# 3_RK3588_POWER.net
KiCad netlist of a schematic drawn in Altium Designer
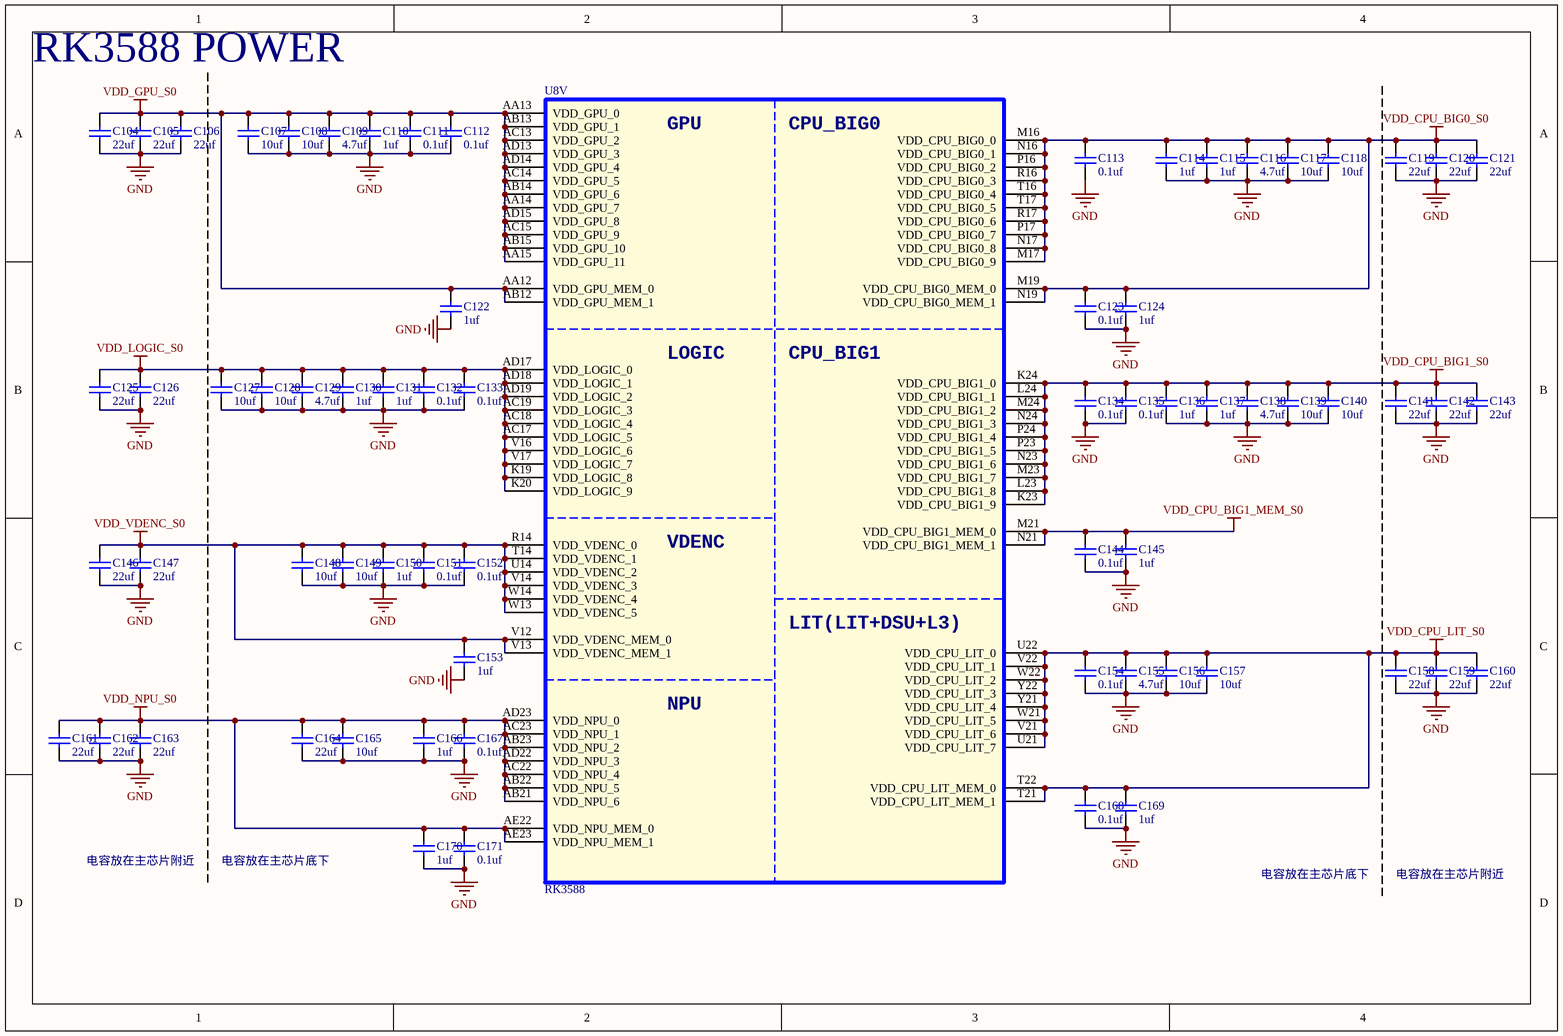
[diagram p0: 3.RK3588_POWER.SchDoc]

(export (version "E")
  (design (tool "Eeschema 10.0.6"))
  (components
    (comp (ref "C104")
      (value "22uf")
      (footprint "0.PCB1:C0603_L")
      (description "贴片电容/MLCC电容")
      (libsource (lib "RK3588") (part "C"))
    )
    (comp (ref "C105")
      (value "22uf")
      (footprint "0.PCB1:C0603_L")
      (description "贴片电容/MLCC电容")
      (libsource (lib "RK3588") (part "C"))
    )
    (comp (ref "C106")
      (value "22uf")
      (footprint "0.PCB1:C0603_L")
      (description "贴片电容/MLCC电容")
      (libsource (lib "RK3588") (part "C"))
    )
    (comp (ref "C107")
      (value "10uf")
      (footprint "0.PCB1:C0402_L")
      (description "贴片电容/MLCC电容")
      (libsource (lib "RK3588") (part "C"))
    )
    (comp (ref "C108")
      (value "10uf")
      (footprint "0.PCB1:C0402_L")
      (description "贴片电容/MLCC电容")
      (libsource (lib "RK3588") (part "C"))
    )
    (comp (ref "C109")
      (value "4.7uf")
      (footprint "0.PCB1:C0402_L")
      (description "贴片电容/MLCC电容")
      (libsource (lib "RK3588") (part "C"))
    )
    (comp (ref "C110")
      (value "1uf")
      (footprint "0.PCB1:C0201_L")
      (description "贴片电容/MLCC电容")
      (libsource (lib "RK3588") (part "C"))
    )
    (comp (ref "C111")
      (value "0.1uf")
      (footprint "0.PCB1:C0201_L")
      (description "贴片电容/MLCC电容")
      (libsource (lib "RK3588") (part "C"))
    )
    (comp (ref "C112")
      (value "0.1uf")
      (footprint "0.PCB1:C0201_L")
      (description "贴片电容/MLCC电容")
      (libsource (lib "RK3588") (part "C"))
    )
    (comp (ref "C113")
      (value "0.1uf")
      (footprint "0.PCB1:C0201_L")
      (description "贴片电容/MLCC电容")
      (libsource (lib "RK3588") (part "C"))
    )
    (comp (ref "C114")
      (value "1uf")
      (footprint "0.PCB1:C0201_L")
      (description "贴片电容/MLCC电容")
      (libsource (lib "RK3588") (part "C"))
    )
    (comp (ref "C115")
      (value "1uf")
      (footprint "0.PCB1:C0201_L")
      (description "贴片电容/MLCC电容")
      (libsource (lib "RK3588") (part "C"))
    )
    (comp (ref "C116")
      (value "4.7uf")
      (footprint "0.PCB1:C0201_L")
      (description "贴片电容/MLCC电容")
      (libsource (lib "RK3588") (part "C"))
    )
    (comp (ref "C117")
      (value "10uf")
      (footprint "0.PCB1:C0402_L")
      (description "贴片电容/MLCC电容")
      (libsource (lib "RK3588") (part "C"))
    )
    (comp (ref "C118")
      (value "10uf")
      (footprint "0.PCB1:C0402_L")
      (description "贴片电容/MLCC电容")
      (libsource (lib "RK3588") (part "C"))
    )
    (comp (ref "C119")
      (value "22uf")
      (footprint "0.PCB1:C0603_L")
      (description "贴片电容/MLCC电容")
      (libsource (lib "RK3588") (part "C"))
    )
    (comp (ref "C120")
      (value "22uf")
      (footprint "0.PCB1:C0603_L")
      (description "贴片电容/MLCC电容")
      (libsource (lib "RK3588") (part "C"))
    )
    (comp (ref "C121")
      (value "22uf")
      (footprint "0.PCB1:C0603_L")
      (description "贴片电容/MLCC电容")
      (libsource (lib "RK3588") (part "C"))
    )
    (comp (ref "C122")
      (value "1uf")
      (footprint "0.PCB1:C0201_L")
      (description "贴片电容/MLCC电容")
      (libsource (lib "RK3588") (part "C"))
    )
    (comp (ref "C123")
      (value "0.1uf")
      (footprint "0.PCB1:C0201_L")
      (description "贴片电容/MLCC电容")
      (libsource (lib "RK3588") (part "C"))
    )
    (comp (ref "C124")
      (value "1uf")
      (footprint "0.PCB1:C0201_L")
      (description "贴片电容/MLCC电容")
      (libsource (lib "RK3588") (part "C"))
    )
    (comp (ref "C125")
      (value "22uf")
      (footprint "0.PCB1:C0603_L")
      (description "贴片电容/MLCC电容")
      (libsource (lib "RK3588") (part "C"))
    )
    (comp (ref "C126")
      (value "22uf")
      (footprint "0.PCB1:C0603_L")
      (description "贴片电容/MLCC电容")
      (libsource (lib "RK3588") (part "C"))
    )
    (comp (ref "C127")
      (value "10uf")
      (footprint "0.PCB1:C0402_L")
      (description "贴片电容/MLCC电容")
      (libsource (lib "RK3588") (part "C"))
    )
    (comp (ref "C128")
      (value "10uf")
      (footprint "0.PCB1:C0402_L")
      (description "贴片电容/MLCC电容")
      (libsource (lib "RK3588") (part "C"))
    )
    (comp (ref "C129")
      (value "4.7uf")
      (footprint "0.PCB1:C0402_L")
      (description "贴片电容/MLCC电容")
      (libsource (lib "RK3588") (part "C"))
    )
    (comp (ref "C130")
      (value "1uf")
      (footprint "0.PCB1:C0201_L")
      (description "贴片电容/MLCC电容")
      (libsource (lib "RK3588") (part "C"))
    )
    (comp (ref "C131")
      (value "1uf")
      (footprint "0.PCB1:C0201_L")
      (description "贴片电容/MLCC电容")
      (libsource (lib "RK3588") (part "C"))
    )
    (comp (ref "C132")
      (value "0.1uf")
      (footprint "0.PCB1:C0201_L")
      (description "贴片电容/MLCC电容")
      (libsource (lib "RK3588") (part "C"))
    )
    (comp (ref "C133")
      (value "0.1uf")
      (footprint "0.PCB1:C0201_L")
      (description "贴片电容/MLCC电容")
      (libsource (lib "RK3588") (part "C"))
    )
    (comp (ref "C134")
      (value "0.1uf")
      (footprint "0.PCB1:C0201_L")
      (description "贴片电容/MLCC电容")
      (libsource (lib "RK3588") (part "C"))
    )
    (comp (ref "C135")
      (value "0.1uf")
      (footprint "0.PCB1:C0201_L")
      (description "贴片电容/MLCC电容")
      (libsource (lib "RK3588") (part "C"))
    )
    (comp (ref "C136")
      (value "1uf")
      (footprint "0.PCB1:C0201_L")
      (description "贴片电容/MLCC电容")
      (libsource (lib "RK3588") (part "C"))
    )
    (comp (ref "C137")
      (value "1uf")
      (footprint "0.PCB1:C0201_L")
      (description "贴片电容/MLCC电容")
      (libsource (lib "RK3588") (part "C"))
    )
    (comp (ref "C138")
      (value "4.7uf")
      (footprint "0.PCB1:C0402_L")
      (description "贴片电容/MLCC电容")
      (libsource (lib "RK3588") (part "C"))
    )
    (comp (ref "C139")
      (value "10uf")
      (footprint "0.PCB1:C0402_L")
      (description "贴片电容/MLCC电容")
      (libsource (lib "RK3588") (part "C"))
    )
    (comp (ref "C140")
      (value "10uf")
      (footprint "0.PCB1:C0402_L")
      (description "贴片电容/MLCC电容")
      (libsource (lib "RK3588") (part "C"))
    )
    (comp (ref "C141")
      (value "22uf")
      (footprint "0.PCB1:C0603_L")
      (description "贴片电容/MLCC电容")
      (libsource (lib "RK3588") (part "C"))
    )
    (comp (ref "C142")
      (value "22uf")
      (footprint "0.PCB1:C0603_L")
      (description "贴片电容/MLCC电容")
      (libsource (lib "RK3588") (part "C"))
    )
    (comp (ref "C143")
      (value "22uf")
      (footprint "0.PCB1:C0603_L")
      (description "贴片电容/MLCC电容")
      (libsource (lib "RK3588") (part "C"))
    )
    (comp (ref "C144")
      (value "0.1uf")
      (footprint "0.PCB1:C0201_L")
      (description "贴片电容/MLCC电容")
      (libsource (lib "RK3588") (part "C"))
    )
    (comp (ref "C145")
      (value "1uf")
      (footprint "0.PCB1:C0201_L")
      (description "贴片电容/MLCC电容")
      (libsource (lib "RK3588") (part "C"))
    )
    (comp (ref "C146")
      (value "22uf")
      (footprint "0.PCB1:C0603_L")
      (description "贴片电容/MLCC电容")
      (libsource (lib "RK3588") (part "C"))
    )
    (comp (ref "C147")
      (value "22uf")
      (footprint "0.PCB1:C0603_L")
      (description "贴片电容/MLCC电容")
      (libsource (lib "RK3588") (part "C"))
    )
    (comp (ref "C148")
      (value "10uf")
      (footprint "0.PCB1:C0402_L")
      (description "贴片电容/MLCC电容")
      (libsource (lib "RK3588") (part "C"))
    )
    (comp (ref "C149")
      (value "10uf")
      (footprint "0.PCB1:C0402_L")
      (description "贴片电容/MLCC电容")
      (libsource (lib "RK3588") (part "C"))
    )
    (comp (ref "C150")
      (value "1uf")
      (footprint "0.PCB1:C0201_L")
      (description "贴片电容/MLCC电容")
      (libsource (lib "RK3588") (part "C"))
    )
    (comp (ref "C151")
      (value "0.1uf")
      (footprint "0.PCB1:C0201_L")
      (description "贴片电容/MLCC电容")
      (libsource (lib "RK3588") (part "C"))
    )
    (comp (ref "C152")
      (value "0.1uf")
      (footprint "0.PCB1:C0201_L")
      (description "贴片电容/MLCC电容")
      (libsource (lib "RK3588") (part "C"))
    )
    (comp (ref "C153")
      (value "1uf")
      (footprint "0.PCB1:C0201_L")
      (description "贴片电容/MLCC电容")
      (libsource (lib "RK3588") (part "C"))
    )
    (comp (ref "C154")
      (value "0.1uf")
      (footprint "0.PCB1:C0201_L")
      (description "贴片电容/MLCC电容")
      (libsource (lib "RK3588") (part "C"))
    )
    (comp (ref "C155")
      (value "4.7uf")
      (footprint "0.PCB1:C0402_L")
      (description "贴片电容/MLCC电容")
      (libsource (lib "RK3588") (part "C"))
    )
    (comp (ref "C156")
      (value "10uf")
      (footprint "0.PCB1:C0402_L")
      (description "贴片电容/MLCC电容")
      (libsource (lib "RK3588") (part "C"))
    )
    (comp (ref "C157")
      (value "10uf")
      (footprint "0.PCB1:C0402_L")
      (description "贴片电容/MLCC电容")
      (libsource (lib "RK3588") (part "C"))
    )
    (comp (ref "C158")
      (value "22uf")
      (footprint "0.PCB1:C0603_L")
      (description "贴片电容/MLCC电容")
      (libsource (lib "RK3588") (part "C"))
    )
    (comp (ref "C159")
      (value "22uf")
      (footprint "0.PCB1:C0603_L")
      (description "贴片电容/MLCC电容")
      (libsource (lib "RK3588") (part "C"))
    )
    (comp (ref "C160")
      (value "22uf")
      (footprint "0.PCB1:C0603_L")
      (description "贴片电容/MLCC电容")
      (libsource (lib "RK3588") (part "C"))
    )
    (comp (ref "C161")
      (value "22uf")
      (footprint "0.PCB1:C0603_L")
      (description "贴片电容/MLCC电容")
      (libsource (lib "RK3588") (part "C"))
    )
    (comp (ref "C162")
      (value "22uf")
      (footprint "0.PCB1:C0603_L")
      (description "贴片电容/MLCC电容")
      (libsource (lib "RK3588") (part "C"))
    )
    (comp (ref "C163")
      (value "22uf")
      (footprint "0.PCB1:C0603_L")
      (description "贴片电容/MLCC电容")
      (libsource (lib "RK3588") (part "C"))
    )
    (comp (ref "C164")
      (value "22uf")
      (footprint "0.PCB1:C0402_L")
      (description "贴片电容/MLCC电容")
      (libsource (lib "RK3588") (part "C"))
    )
    (comp (ref "C165")
      (value "10uf")
      (footprint "0.PCB1:C0402_L")
      (description "贴片电容/MLCC电容")
      (libsource (lib "RK3588") (part "C"))
    )
    (comp (ref "C166")
      (value "1uf")
      (footprint "0.PCB1:C0201_L")
      (description "贴片电容/MLCC电容")
      (libsource (lib "RK3588") (part "C"))
    )
    (comp (ref "C167")
      (value "0.1uf")
      (footprint "0.PCB1:C0201_L")
      (description "贴片电容/MLCC电容")
      (libsource (lib "RK3588") (part "C"))
    )
    (comp (ref "C168")
      (value "0.1uf")
      (footprint "0.PCB1:C0201_L")
      (description "贴片电容/MLCC电容")
      (libsource (lib "RK3588") (part "C"))
    )
    (comp (ref "C169")
      (value "1uf")
      (footprint "0.PCB1:C0201_L")
      (description "贴片电容/MLCC电容")
      (libsource (lib "RK3588") (part "C"))
    )
    (comp (ref "C170")
      (value "1uf")
      (footprint "0.PCB1:C0201_L")
      (description "贴片电容/MLCC电容")
      (libsource (lib "RK3588") (part "C"))
    )
    (comp (ref "C171")
      (value "0.1uf")
      (footprint "0.PCB1:C0201_L")
      (description "贴片电容/MLCC电容")
      (libsource (lib "RK3588") (part "C"))
    )
    (comp (ref "U8")
      (value "RK3588")
      (footprint "0.PCB1:BGA1088_23R00X23R00X2R00")
      (description "ROCKCHIP SOC")
      (libsource (lib "RK3588") (part "SOC_RK3588"))
    )
  )
  (nets
    (net (code "1") (name "GND") (class "Default")
      (node (ref "C104") (pin "1") (pinfunction "1_1") (pintype "passive"))
      (node (ref "C105") (pin "1") (pinfunction "1_1") (pintype "passive"))
      (node (ref "C106") (pin "1") (pinfunction "1_1") (pintype "passive"))
      (node (ref "C107") (pin "1") (pinfunction "1_1") (pintype "passive"))
      (node (ref "C108") (pin "1") (pinfunction "1_1") (pintype "passive"))
      (node (ref "C109") (pin "1") (pinfunction "1_1") (pintype "passive"))
      (node (ref "C110") (pin "1") (pinfunction "1_1") (pintype "passive"))
      (node (ref "C111") (pin "1") (pinfunction "1_1") (pintype "passive"))
      (node (ref "C112") (pin "1") (pinfunction "1_1") (pintype "passive"))
      (node (ref "C113") (pin "1") (pinfunction "1_1") (pintype "passive"))
      (node (ref "C114") (pin "1") (pinfunction "1_1") (pintype "passive"))
      (node (ref "C115") (pin "1") (pinfunction "1_1") (pintype "passive"))
      (node (ref "C116") (pin "1") (pinfunction "1_1") (pintype "passive"))
      (node (ref "C117") (pin "1") (pinfunction "1_1") (pintype "passive"))
      (node (ref "C118") (pin "1") (pinfunction "1_1") (pintype "passive"))
      (node (ref "C119") (pin "1") (pinfunction "1_1") (pintype "passive"))
      (node (ref "C120") (pin "1") (pinfunction "1_1") (pintype "passive"))
      (node (ref "C121") (pin "1") (pinfunction "1_1") (pintype "passive"))
      (node (ref "C122") (pin "1") (pinfunction "1_1") (pintype "passive"))
      (node (ref "C123") (pin "1") (pinfunction "1_1") (pintype "passive"))
      (node (ref "C124") (pin "1") (pinfunction "1_1") (pintype "passive"))
      (node (ref "C125") (pin "1") (pinfunction "1_1") (pintype "passive"))
      (node (ref "C126") (pin "1") (pinfunction "1_1") (pintype "passive"))
      (node (ref "C127") (pin "1") (pinfunction "1_1") (pintype "passive"))
      (node (ref "C128") (pin "1") (pinfunction "1_1") (pintype "passive"))
      (node (ref "C129") (pin "1") (pinfunction "1_1") (pintype "passive"))
      (node (ref "C130") (pin "1") (pinfunction "1_1") (pintype "passive"))
      (node (ref "C131") (pin "1") (pinfunction "1_1") (pintype "passive"))
      (node (ref "C132") (pin "1") (pinfunction "1_1") (pintype "passive"))
      (node (ref "C133") (pin "1") (pinfunction "1_1") (pintype "passive"))
      (node (ref "C134") (pin "1") (pinfunction "1_1") (pintype "passive"))
      (node (ref "C135") (pin "1") (pinfunction "1_1") (pintype "passive"))
      (node (ref "C136") (pin "1") (pinfunction "1_1") (pintype "passive"))
      (node (ref "C137") (pin "1") (pinfunction "1_1") (pintype "passive"))
      (node (ref "C138") (pin "1") (pinfunction "1_1") (pintype "passive"))
      (node (ref "C139") (pin "1") (pinfunction "1_1") (pintype "passive"))
      (node (ref "C140") (pin "1") (pinfunction "1_1") (pintype "passive"))
      (node (ref "C141") (pin "1") (pinfunction "1_1") (pintype "passive"))
      (node (ref "C142") (pin "1") (pinfunction "1_1") (pintype "passive"))
      (node (ref "C143") (pin "1") (pinfunction "1_1") (pintype "passive"))
      (node (ref "C144") (pin "1") (pinfunction "1_1") (pintype "passive"))
      (node (ref "C145") (pin "1") (pinfunction "1_1") (pintype "passive"))
      (node (ref "C146") (pin "1") (pinfunction "1_1") (pintype "passive"))
      (node (ref "C147") (pin "1") (pinfunction "1_1") (pintype "passive"))
      (node (ref "C148") (pin "1") (pinfunction "1_1") (pintype "passive"))
      (node (ref "C149") (pin "1") (pinfunction "1_1") (pintype "passive"))
      (node (ref "C150") (pin "1") (pinfunction "1_1") (pintype "passive"))
      (node (ref "C151") (pin "1") (pinfunction "1_1") (pintype "passive"))
      (node (ref "C152") (pin "1") (pinfunction "1_1") (pintype "passive"))
      (node (ref "C153") (pin "1") (pinfunction "1_1") (pintype "passive"))
      (node (ref "C154") (pin "1") (pinfunction "1_1") (pintype "passive"))
      (node (ref "C155") (pin "1") (pinfunction "1_1") (pintype "passive"))
      (node (ref "C156") (pin "1") (pinfunction "1_1") (pintype "passive"))
      (node (ref "C157") (pin "1") (pinfunction "1_1") (pintype "passive"))
      (node (ref "C158") (pin "1") (pinfunction "1_1") (pintype "passive"))
      (node (ref "C159") (pin "1") (pinfunction "1_1") (pintype "passive"))
      (node (ref "C160") (pin "1") (pinfunction "1_1") (pintype "passive"))
      (node (ref "C161") (pin "1") (pinfunction "1_1") (pintype "passive"))
      (node (ref "C162") (pin "1") (pinfunction "1_1") (pintype "passive"))
      (node (ref "C163") (pin "1") (pinfunction "1_1") (pintype "passive"))
      (node (ref "C164") (pin "1") (pinfunction "1_1") (pintype "passive"))
      (node (ref "C165") (pin "1") (pinfunction "1_1") (pintype "passive"))
      (node (ref "C166") (pin "1") (pinfunction "1_1") (pintype "passive"))
      (node (ref "C167") (pin "1") (pinfunction "1_1") (pintype "passive"))
      (node (ref "C168") (pin "1") (pinfunction "1_1") (pintype "passive"))
      (node (ref "C169") (pin "1") (pinfunction "1_1") (pintype "passive"))
      (node (ref "C170") (pin "1") (pinfunction "1_1") (pintype "passive"))
      (node (ref "C171") (pin "1") (pinfunction "1_1") (pintype "passive"))
    )
    (net (code "2") (name "VDD_CPU_BIG0_S0") (class "Default")
      (node (ref "C113") (pin "2") (pinfunction "2_2") (pintype "passive"))
      (node (ref "C114") (pin "2") (pinfunction "2_2") (pintype "passive"))
      (node (ref "C115") (pin "2") (pinfunction "2_2") (pintype "passive"))
      (node (ref "C116") (pin "2") (pinfunction "2_2") (pintype "passive"))
      (node (ref "C117") (pin "2") (pinfunction "2_2") (pintype "passive"))
      (node (ref "C118") (pin "2") (pinfunction "2_2") (pintype "passive"))
      (node (ref "C119") (pin "2") (pinfunction "2_2") (pintype "passive"))
      (node (ref "C120") (pin "2") (pinfunction "2_2") (pintype "passive"))
      (node (ref "C121") (pin "2") (pinfunction "2_2") (pintype "passive"))
      (node (ref "C123") (pin "2") (pinfunction "2_2") (pintype "passive"))
      (node (ref "C124") (pin "2") (pinfunction "2_2") (pintype "passive"))
      (node (ref "U8") (pin "M16") (pinfunction "VDD_CPU_BIG0_0_M16") (pintype "power_in"))
      (node (ref "U8") (pin "M17") (pinfunction "VDD_CPU_BIG0_9_M17") (pintype "power_in"))
      (node (ref "U8") (pin "M19") (pinfunction "VDD_CPU_BIG0_MEM_0_M19") (pintype "power_in"))
      (node (ref "U8") (pin "N16") (pinfunction "VDD_CPU_BIG0_1_N16") (pintype "power_in"))
      (node (ref "U8") (pin "N17") (pinfunction "VDD_CPU_BIG0_8_N17") (pintype "power_in"))
      (node (ref "U8") (pin "N19") (pinfunction "VDD_CPU_BIG0_MEM_1_N19") (pintype "power_in"))
      (node (ref "U8") (pin "P16") (pinfunction "VDD_CPU_BIG0_2_P16") (pintype "power_in"))
      (node (ref "U8") (pin "P17") (pinfunction "VDD_CPU_BIG0_7_P17") (pintype "power_in"))
      (node (ref "U8") (pin "R16") (pinfunction "VDD_CPU_BIG0_3_R16") (pintype "power_in"))
      (node (ref "U8") (pin "R17") (pinfunction "VDD_CPU_BIG0_6_R17") (pintype "power_in"))
      (node (ref "U8") (pin "T16") (pinfunction "VDD_CPU_BIG0_4_T16") (pintype "power_in"))
      (node (ref "U8") (pin "T17") (pinfunction "VDD_CPU_BIG0_5_T17") (pintype "power_in"))
    )
    (net (code "3") (name "VDD_CPU_BIG1_MEM_S0") (class "Default")
      (node (ref "C144") (pin "2") (pinfunction "2_2") (pintype "passive"))
      (node (ref "C145") (pin "2") (pinfunction "2_2") (pintype "passive"))
      (node (ref "U8") (pin "M21") (pinfunction "VDD_CPU_BIG1_MEM_0_M21") (pintype "power_in"))
      (node (ref "U8") (pin "N21") (pinfunction "VDD_CPU_BIG1_MEM_1_N21") (pintype "power_in"))
    )
    (net (code "4") (name "VDD_CPU_BIG1_S0") (class "Default")
      (node (ref "C134") (pin "2") (pinfunction "2_2") (pintype "passive"))
      (node (ref "C135") (pin "2") (pinfunction "2_2") (pintype "passive"))
      (node (ref "C136") (pin "2") (pinfunction "2_2") (pintype "passive"))
      (node (ref "C137") (pin "2") (pinfunction "2_2") (pintype "passive"))
      (node (ref "C138") (pin "2") (pinfunction "2_2") (pintype "passive"))
      (node (ref "C139") (pin "2") (pinfunction "2_2") (pintype "passive"))
      (node (ref "C140") (pin "2") (pinfunction "2_2") (pintype "passive"))
      (node (ref "C141") (pin "2") (pinfunction "2_2") (pintype "passive"))
      (node (ref "C142") (pin "2") (pinfunction "2_2") (pintype "passive"))
      (node (ref "C143") (pin "2") (pinfunction "2_2") (pintype "passive"))
      (node (ref "U8") (pin "K23") (pinfunction "VDD_CPU_BIG1_9_K23") (pintype "power_in"))
      (node (ref "U8") (pin "K24") (pinfunction "VDD_CPU_BIG1_0_K24") (pintype "power_in"))
      (node (ref "U8") (pin "L23") (pinfunction "VDD_CPU_BIG1_8_L23") (pintype "power_in"))
      (node (ref "U8") (pin "L24") (pinfunction "VDD_CPU_BIG1_1_L24") (pintype "power_in"))
      (node (ref "U8") (pin "M23") (pinfunction "VDD_CPU_BIG1_7_M23") (pintype "power_in"))
      (node (ref "U8") (pin "M24") (pinfunction "VDD_CPU_BIG1_2_M24") (pintype "power_in"))
      (node (ref "U8") (pin "N23") (pinfunction "VDD_CPU_BIG1_6_N23") (pintype "power_in"))
      (node (ref "U8") (pin "N24") (pinfunction "VDD_CPU_BIG1_3_N24") (pintype "power_in"))
      (node (ref "U8") (pin "P23") (pinfunction "VDD_CPU_BIG1_5_P23") (pintype "power_in"))
      (node (ref "U8") (pin "P24") (pinfunction "VDD_CPU_BIG1_4_P24") (pintype "power_in"))
    )
    (net (code "5") (name "VDD_CPU_LIT_S0") (class "Default")
      (node (ref "C154") (pin "2") (pinfunction "2_2") (pintype "passive"))
      (node (ref "C155") (pin "2") (pinfunction "2_2") (pintype "passive"))
      (node (ref "C156") (pin "2") (pinfunction "2_2") (pintype "passive"))
      (node (ref "C157") (pin "2") (pinfunction "2_2") (pintype "passive"))
      (node (ref "C158") (pin "2") (pinfunction "2_2") (pintype "passive"))
      (node (ref "C159") (pin "2") (pinfunction "2_2") (pintype "passive"))
      (node (ref "C160") (pin "2") (pinfunction "2_2") (pintype "passive"))
      (node (ref "C168") (pin "2") (pinfunction "2_2") (pintype "passive"))
      (node (ref "C169") (pin "2") (pinfunction "2_2") (pintype "passive"))
      (node (ref "U8") (pin "T21") (pinfunction "VDD_CPU_LIT_MEM_1_T21") (pintype "power_in"))
      (node (ref "U8") (pin "T22") (pinfunction "VDD_CPU_LIT_MEM_0_T22") (pintype "power_in"))
      (node (ref "U8") (pin "U21") (pinfunction "VDD_CPU_LIT_7_U21") (pintype "power_in"))
      (node (ref "U8") (pin "U22") (pinfunction "VDD_CPU_LIT_0_U22") (pintype "power_in"))
      (node (ref "U8") (pin "V21") (pinfunction "VDD_CPU_LIT_6_V21") (pintype "power_in"))
      (node (ref "U8") (pin "V22") (pinfunction "VDD_CPU_LIT_1_V22") (pintype "power_in"))
      (node (ref "U8") (pin "W21") (pinfunction "VDD_CPU_LIT_5_W21") (pintype "power_in"))
      (node (ref "U8") (pin "W22") (pinfunction "VDD_CPU_LIT_2_W22") (pintype "power_in"))
      (node (ref "U8") (pin "Y21") (pinfunction "VDD_CPU_LIT_4_Y21") (pintype "power_in"))
      (node (ref "U8") (pin "Y22") (pinfunction "VDD_CPU_LIT_3_Y22") (pintype "power_in"))
    )
    (net (code "6") (name "VDD_GPU_S0") (class "Default")
      (node (ref "C104") (pin "2") (pinfunction "2_2") (pintype "passive"))
      (node (ref "C105") (pin "2") (pinfunction "2_2") (pintype "passive"))
      (node (ref "C106") (pin "2") (pinfunction "2_2") (pintype "passive"))
      (node (ref "C107") (pin "2") (pinfunction "2_2") (pintype "passive"))
      (node (ref "C108") (pin "2") (pinfunction "2_2") (pintype "passive"))
      (node (ref "C109") (pin "2") (pinfunction "2_2") (pintype "passive"))
      (node (ref "C110") (pin "2") (pinfunction "2_2") (pintype "passive"))
      (node (ref "C111") (pin "2") (pinfunction "2_2") (pintype "passive"))
      (node (ref "C112") (pin "2") (pinfunction "2_2") (pintype "passive"))
      (node (ref "C122") (pin "2") (pinfunction "2_2") (pintype "passive"))
      (node (ref "U8") (pin "AA12") (pinfunction "VDD_GPU_MEM_0_AA12") (pintype "power_in"))
      (node (ref "U8") (pin "AA13") (pinfunction "VDD_GPU_0_AA13") (pintype "power_in"))
      (node (ref "U8") (pin "AA14") (pinfunction "VDD_GPU_7_AA14") (pintype "power_in"))
      (node (ref "U8") (pin "AA15") (pinfunction "VDD_GPU_11_AA15") (pintype "power_in"))
      (node (ref "U8") (pin "AB12") (pinfunction "VDD_GPU_MEM_1_AB12") (pintype "power_in"))
      (node (ref "U8") (pin "AB13") (pinfunction "VDD_GPU_1_AB13") (pintype "power_in"))
      (node (ref "U8") (pin "AB14") (pinfunction "VDD_GPU_6_AB14") (pintype "power_in"))
      (node (ref "U8") (pin "AB15") (pinfunction "VDD_GPU_10_AB15") (pintype "power_in"))
      (node (ref "U8") (pin "AC13") (pinfunction "VDD_GPU_2_AC13") (pintype "power_in"))
      (node (ref "U8") (pin "AC14") (pinfunction "VDD_GPU_5_AC14") (pintype "power_in"))
      (node (ref "U8") (pin "AC15") (pinfunction "VDD_GPU_9_AC15") (pintype "power_in"))
      (node (ref "U8") (pin "AD13") (pinfunction "VDD_GPU_3_AD13") (pintype "power_in"))
      (node (ref "U8") (pin "AD14") (pinfunction "VDD_GPU_4_AD14") (pintype "power_in"))
      (node (ref "U8") (pin "AD15") (pinfunction "VDD_GPU_8_AD15") (pintype "power_in"))
    )
    (net (code "7") (name "VDD_LOGIC_S0") (class "Default")
      (node (ref "C125") (pin "2") (pinfunction "2_2") (pintype "passive"))
      (node (ref "C126") (pin "2") (pinfunction "2_2") (pintype "passive"))
      (node (ref "C127") (pin "2") (pinfunction "2_2") (pintype "passive"))
      (node (ref "C128") (pin "2") (pinfunction "2_2") (pintype "passive"))
      (node (ref "C129") (pin "2") (pinfunction "2_2") (pintype "passive"))
      (node (ref "C130") (pin "2") (pinfunction "2_2") (pintype "passive"))
      (node (ref "C131") (pin "2") (pinfunction "2_2") (pintype "passive"))
      (node (ref "C132") (pin "2") (pinfunction "2_2") (pintype "passive"))
      (node (ref "C133") (pin "2") (pinfunction "2_2") (pintype "passive"))
      (node (ref "U8") (pin "AC17") (pinfunction "VDD_LOGIC_5_AC17") (pintype "power_in"))
      (node (ref "U8") (pin "AC18") (pinfunction "VDD_LOGIC_4_AC18") (pintype "power_in"))
      (node (ref "U8") (pin "AC19") (pinfunction "VDD_LOGIC_3_AC19") (pintype "power_in"))
      (node (ref "U8") (pin "AD17") (pinfunction "VDD_LOGIC_0_AD17") (pintype "power_in"))
      (node (ref "U8") (pin "AD18") (pinfunction "VDD_LOGIC_1_AD18") (pintype "power_in"))
      (node (ref "U8") (pin "AD19") (pinfunction "VDD_LOGIC_2_AD19") (pintype "power_in"))
      (node (ref "U8") (pin "K19") (pinfunction "VDD_LOGIC_8_K19") (pintype "power_in"))
      (node (ref "U8") (pin "K20") (pinfunction "VDD_LOGIC_9_K20") (pintype "power_in"))
      (node (ref "U8") (pin "V16") (pinfunction "VDD_LOGIC_6_V16") (pintype "power_in"))
      (node (ref "U8") (pin "V17") (pinfunction "VDD_LOGIC_7_V17") (pintype "power_in"))
    )
    (net (code "8") (name "VDD_NPU_S0") (class "Default")
      (node (ref "C161") (pin "2") (pinfunction "2_2") (pintype "passive"))
      (node (ref "C162") (pin "2") (pinfunction "2_2") (pintype "passive"))
      (node (ref "C163") (pin "2") (pinfunction "2_2") (pintype "passive"))
      (node (ref "C164") (pin "2") (pinfunction "2_2") (pintype "passive"))
      (node (ref "C165") (pin "2") (pinfunction "2_2") (pintype "passive"))
      (node (ref "C166") (pin "2") (pinfunction "2_2") (pintype "passive"))
      (node (ref "C167") (pin "2") (pinfunction "2_2") (pintype "passive"))
      (node (ref "C170") (pin "2") (pinfunction "2_2") (pintype "passive"))
      (node (ref "C171") (pin "2") (pinfunction "2_2") (pintype "passive"))
      (node (ref "U8") (pin "AB21") (pinfunction "VDD_NPU_6_AB21") (pintype "power_in"))
      (node (ref "U8") (pin "AB22") (pinfunction "VDD_NPU_5_AB22") (pintype "power_in"))
      (node (ref "U8") (pin "AB23") (pinfunction "VDD_NPU_2_AB23") (pintype "power_in"))
      (node (ref "U8") (pin "AC22") (pinfunction "VDD_NPU_4_AC22") (pintype "power_in"))
      (node (ref "U8") (pin "AC23") (pinfunction "VDD_NPU_1_AC23") (pintype "power_in"))
      (node (ref "U8") (pin "AD22") (pinfunction "VDD_NPU_3_AD22") (pintype "power_in"))
      (node (ref "U8") (pin "AD23") (pinfunction "VDD_NPU_0_AD23") (pintype "power_in"))
      (node (ref "U8") (pin "AE22") (pinfunction "VDD_NPU_MEM_0_AE22") (pintype "power_in"))
      (node (ref "U8") (pin "AE23") (pinfunction "VDD_NPU_MEM_1_AE23") (pintype "power_in"))
    )
    (net (code "9") (name "VDD_VDENC_S0") (class "Default")
      (node (ref "C146") (pin "2") (pinfunction "2_2") (pintype "passive"))
      (node (ref "C147") (pin "2") (pinfunction "2_2") (pintype "passive"))
      (node (ref "C148") (pin "2") (pinfunction "2_2") (pintype "passive"))
      (node (ref "C149") (pin "2") (pinfunction "2_2") (pintype "passive"))
      (node (ref "C150") (pin "2") (pinfunction "2_2") (pintype "passive"))
      (node (ref "C151") (pin "2") (pinfunction "2_2") (pintype "passive"))
      (node (ref "C152") (pin "2") (pinfunction "2_2") (pintype "passive"))
      (node (ref "C153") (pin "2") (pinfunction "2_2") (pintype "passive"))
      (node (ref "U8") (pin "R14") (pinfunction "VDD_VDENC_0_R14") (pintype "power_in"))
      (node (ref "U8") (pin "T14") (pinfunction "VDD_VDENC_1_T14") (pintype "power_in"))
      (node (ref "U8") (pin "U14") (pinfunction "VDD_VDENC_2_U14") (pintype "power_in"))
      (node (ref "U8") (pin "V12") (pinfunction "VDD_VDENC_MEM_0_V12") (pintype "power_in"))
      (node (ref "U8") (pin "V13") (pinfunction "VDD_VDENC_MEM_1_V13") (pintype "power_in"))
      (node (ref "U8") (pin "V14") (pinfunction "VDD_VDENC_3_V14") (pintype "power_in"))
      (node (ref "U8") (pin "W13") (pinfunction "VDD_VDENC_5_W13") (pintype "power_in"))
      (node (ref "U8") (pin "W14") (pinfunction "VDD_VDENC_4_W14") (pintype "power_in"))
    )
  )
)
